# RN41_Rootooth.net
KiCad netlist of a schematic drawn in EAGLE
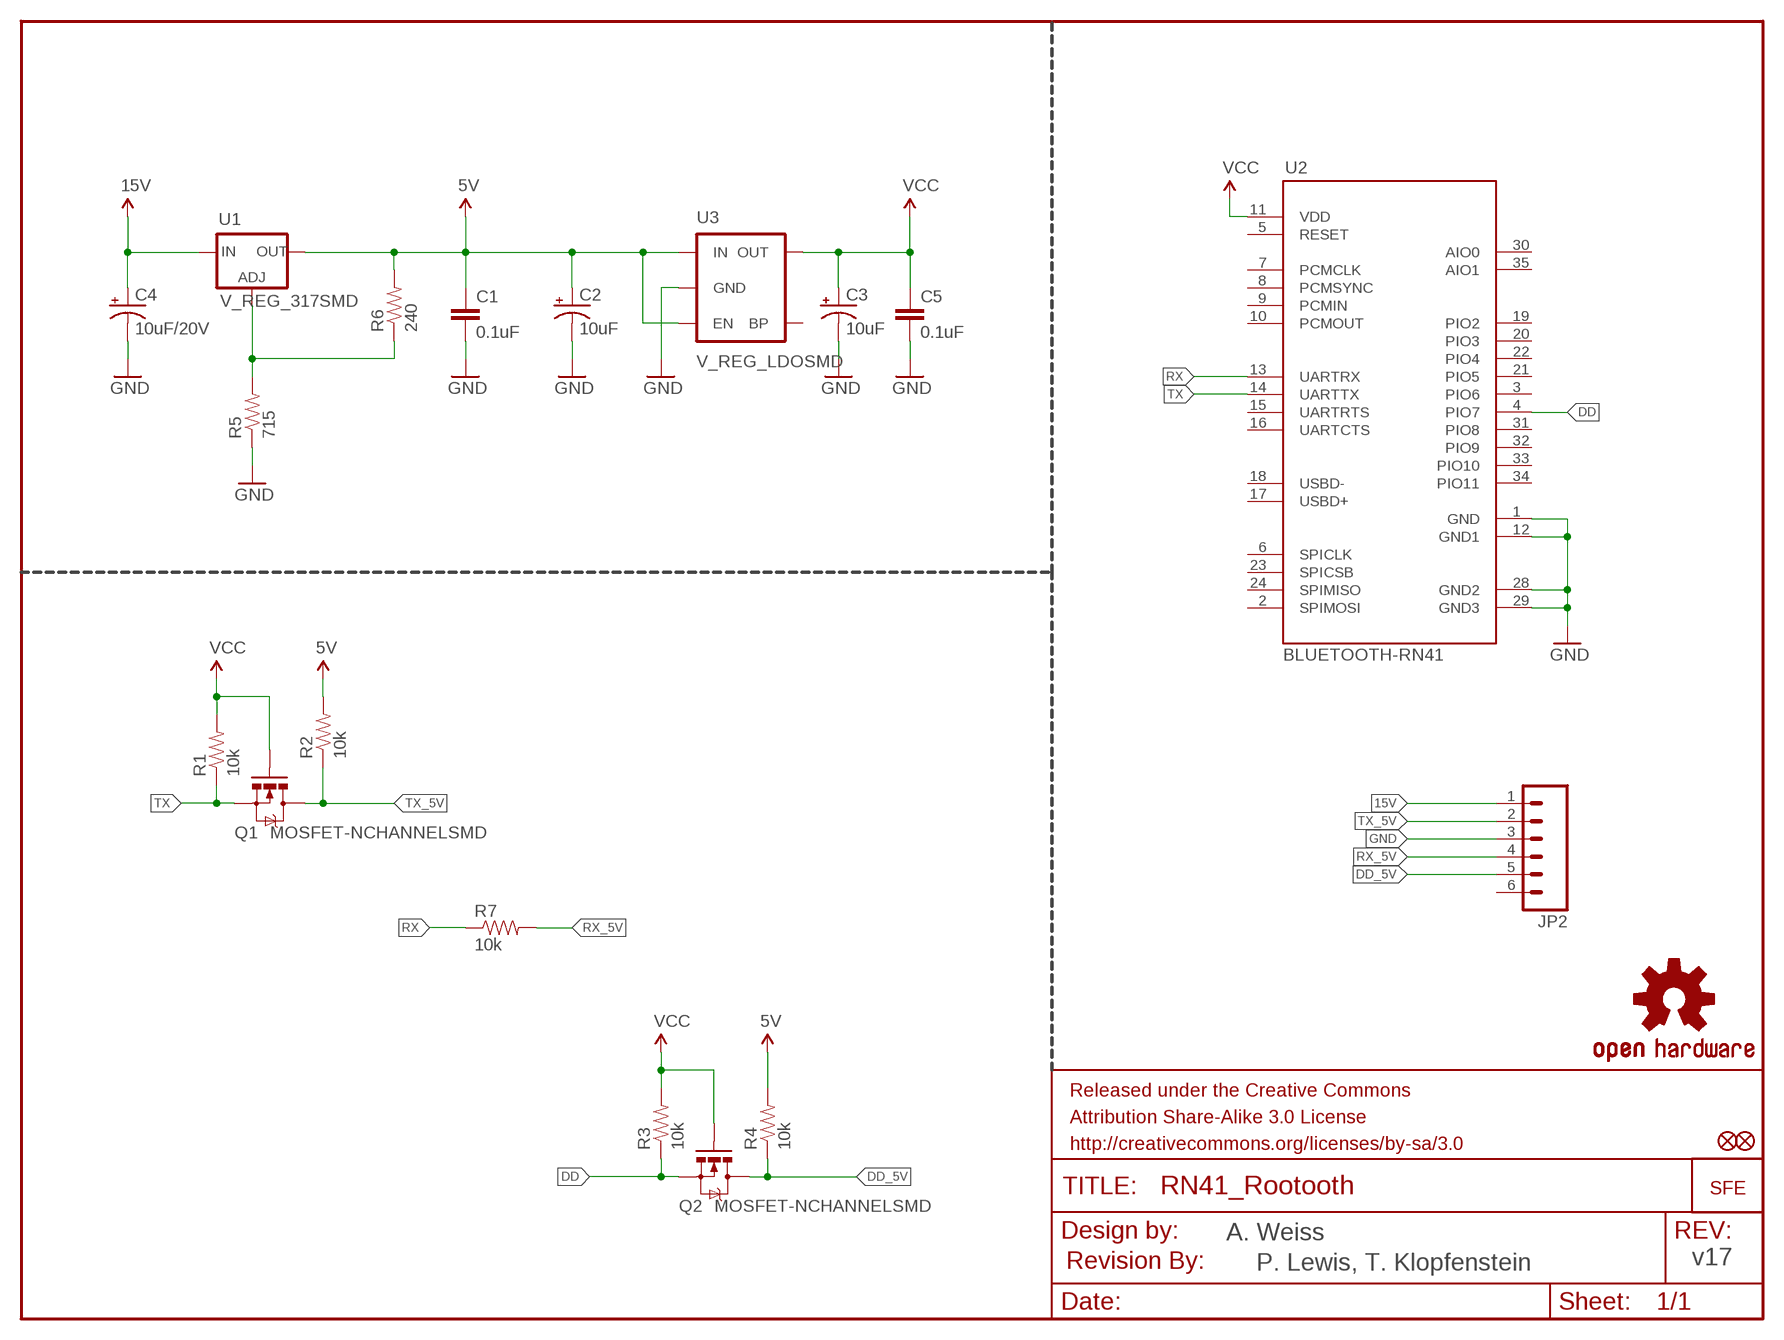
[diagram p0: schematic, sheet 1]

(export (version "E")
  (design (tool "Eeschema 10.0.6"))
  (components
    (comp (ref "C1")
      (value "0.1uF")
      (footprint "eagle-import:0603-CAP")
      (libsource (lib "eagle-import") (part "CAP0603-CAP"))
    )
    (comp (ref "C2")
      (value "10uF")
      (footprint "eagle-import:EIA3216")
      (libsource (lib "eagle-import") (part "CAP_POL1206"))
    )
    (comp (ref "C3")
      (value "10uF")
      (footprint "eagle-import:EIA3216")
      (libsource (lib "eagle-import") (part "CAP_POL1206"))
    )
    (comp (ref "C4")
      (value "10uF/20V")
      (footprint "eagle-import:EIA3528")
      (libsource (lib "eagle-import") (part "CAP_POL3528"))
    )
    (comp (ref "C5")
      (value "0.1uF")
      (footprint "eagle-import:0603-CAP")
      (libsource (lib "eagle-import") (part "CAP0603-CAP"))
    )
    (comp (ref "FRAME1")
      (value "FRAME-LETTER")
      (footprint "eagle-import:CREATIVE_COMMONS")
      (libsource (lib "eagle-import") (part "FRAME-LETTER"))
    )
    (comp (ref "JP1")
      (value "FIDUCIALUFIDUCIAL")
      (footprint "eagle-import:MICRO-FIDUCIAL")
      (libsource (lib "eagle-import") (part "FIDUCIALUFIDUCIAL"))
    )
    (comp (ref "JP2")
      (value "M06SMD")
      (footprint "eagle-import:1X06-SMD")
      (libsource (lib "eagle-import") (part "M06SMD"))
    )
    (comp (ref "JP3")
      (value "FIDUCIALUFIDUCIAL")
      (footprint "eagle-import:MICRO-FIDUCIAL")
      (libsource (lib "eagle-import") (part "FIDUCIALUFIDUCIAL"))
    )
    (comp (ref "LOGO1")
      (value "OSHW-LOGOS")
      (footprint "eagle-import:OSHW-LOGO-S")
      (libsource (lib "eagle-import") (part "OSHW-LOGOS"))
    )
    (comp (ref "Q1")
      (value "MOSFET-NCHANNELSMD")
      (footprint "eagle-import:SOT23-3")
      (libsource (lib "eagle-import") (part "MOSFET-NCHANNELSMD"))
    )
    (comp (ref "Q2")
      (value "MOSFET-NCHANNELSMD")
      (footprint "eagle-import:SOT23-3")
      (libsource (lib "eagle-import") (part "MOSFET-NCHANNELSMD"))
    )
    (comp (ref "R1")
      (value "10k")
      (footprint "eagle-import:0603-RES")
      (libsource (lib "eagle-import") (part "RESISTOR0603-RES"))
    )
    (comp (ref "R2")
      (value "10k")
      (footprint "eagle-import:0603-RES")
      (libsource (lib "eagle-import") (part "RESISTOR0603-RES"))
    )
    (comp (ref "R3")
      (value "10k")
      (footprint "eagle-import:0603-RES")
      (libsource (lib "eagle-import") (part "RESISTOR0603-RES"))
    )
    (comp (ref "R4")
      (value "10k")
      (footprint "eagle-import:0603-RES")
      (libsource (lib "eagle-import") (part "RESISTOR0603-RES"))
    )
    (comp (ref "R5")
      (value "715")
      (footprint "eagle-import:0603-RES")
      (libsource (lib "eagle-import") (part "RESISTOR0603-RES"))
    )
    (comp (ref "R6")
      (value "240")
      (footprint "eagle-import:0603-RES")
      (libsource (lib "eagle-import") (part "RESISTOR0603-RES"))
    )
    (comp (ref "R7")
      (value "10k")
      (footprint "eagle-import:0603-RES")
      (libsource (lib "eagle-import") (part "RESISTOR0603-RES"))
    )
    (comp (ref "U$1")
      (value "LOGO-SFENEW")
      (footprint "eagle-import:SFE-NEW-WEBLOGO")
      (libsource (lib "eagle-import") (part "LOGO-SFENEW"))
    )
    (comp (ref "U$2")
      (value "REVISION")
      (footprint "eagle-import:REVISION")
      (libsource (lib "eagle-import") (part "REVISION"))
    )
    (comp (ref "U1")
      (value "V_REG_317SMD")
      (footprint "eagle-import:SOT223")
      (libsource (lib "eagle-import") (part "V_REG_317SMD"))
    )
    (comp (ref "U2")
      (value "BLUETOOTH-RN41")
      (footprint "eagle-import:RN41")
      (libsource (lib "eagle-import") (part "BLUETOOTH-RN41{dblquote}"))
    )
    (comp (ref "U3")
      (value "V_REG_LDOSMD")
      (footprint "eagle-import:SOT23-5")
      (libsource (lib "eagle-import") (part "V_REG_LDOSMD"))
    )
  )
  (nets
    (net (code "1") (name "5V") (class "Default")
      (node (ref "C1") (pin "1") (pinfunction "1_1") (pintype "passive"))
      (node (ref "C2") (pin "A") (pinfunction "+_A") (pintype "passive"))
      (node (ref "R2") (pin "2") (pinfunction "2_2") (pintype "passive"))
      (node (ref "R4") (pin "2") (pinfunction "2_2") (pintype "passive"))
      (node (ref "R6") (pin "2") (pinfunction "2_2") (pintype "passive"))
      (node (ref "U1") (pin "2") (pinfunction "OUT_2") (pintype "output"))
      (node (ref "U3") (pin "1") (pinfunction "IN_1") (pintype "input"))
      (node (ref "U3") (pin "3") (pinfunction "EN_3") (pintype "input"))
    )
    (net (code "2") (name "15V") (class "Default")
      (node (ref "C4") (pin "A") (pinfunction "+_A") (pintype "passive"))
      (node (ref "JP2") (pin "1") (pinfunction "1_1") (pintype "passive"))
      (node (ref "U1") (pin "3") (pinfunction "IN_3") (pintype "input"))
    )
    (net (code "3") (name "DD") (class "Default")
      (node (ref "Q2") (pin "2") (pinfunction "S_2") (pintype "passive"))
      (node (ref "R3") (pin "1") (pinfunction "1_1") (pintype "passive"))
      (node (ref "U2") (pin "4") (pinfunction "PIO7_4") (pintype "bidirectional"))
    )
    (net (code "4") (name "DD_5V") (class "Default")
      (node (ref "JP2") (pin "5") (pinfunction "5_5") (pintype "passive"))
      (node (ref "Q2") (pin "3") (pinfunction "D_3") (pintype "passive"))
      (node (ref "R4") (pin "1") (pinfunction "1_1") (pintype "passive"))
    )
    (net (code "5") (name "GND") (class "Default")
      (node (ref "C1") (pin "2") (pinfunction "2_2") (pintype "passive"))
      (node (ref "C2") (pin "C") (pinfunction "-_C") (pintype "passive"))
      (node (ref "C3") (pin "C") (pinfunction "-_C") (pintype "passive"))
      (node (ref "C4") (pin "C") (pinfunction "-_C") (pintype "passive"))
      (node (ref "C5") (pin "2") (pinfunction "2_2") (pintype "passive"))
      (node (ref "JP2") (pin "3") (pinfunction "3_3") (pintype "passive"))
      (node (ref "R5") (pin "1") (pinfunction "1_1") (pintype "passive"))
      (node (ref "U2") (pin "1") (pinfunction "GND_1") (pintype "bidirectional"))
      (node (ref "U2") (pin "12") (pinfunction "GND1_12") (pintype "bidirectional"))
      (node (ref "U2") (pin "28") (pinfunction "GND2_28") (pintype "bidirectional"))
      (node (ref "U2") (pin "29") (pinfunction "GND3_29") (pintype "bidirectional"))
      (node (ref "U3") (pin "2") (pinfunction "GND_2") (pintype "input"))
    )
    (net (code "6") (name "Net-(U1-ADJ)") (class "Default")
      (node (ref "R5") (pin "2") (pinfunction "2_2") (pintype "passive"))
      (node (ref "R6") (pin "1") (pinfunction "1_1") (pintype "passive"))
      (node (ref "U1") (pin "1") (pinfunction "ADJ_1") (pintype "input"))
    )
    (net (code "7") (name "RX") (class "Default")
      (node (ref "R7") (pin "1") (pinfunction "1_1") (pintype "passive"))
      (node (ref "U2") (pin "13") (pinfunction "UARTRX_13") (pintype "bidirectional"))
    )
    (net (code "8") (name "RX_5V") (class "Default")
      (node (ref "JP2") (pin "4") (pinfunction "4_4") (pintype "passive"))
      (node (ref "R7") (pin "2") (pinfunction "2_2") (pintype "passive"))
    )
    (net (code "9") (name "TX") (class "Default")
      (node (ref "Q1") (pin "2") (pinfunction "S_2") (pintype "passive"))
      (node (ref "R1") (pin "1") (pinfunction "1_1") (pintype "passive"))
      (node (ref "U2") (pin "14") (pinfunction "UARTTX_14") (pintype "bidirectional"))
    )
    (net (code "10") (name "TX_5V") (class "Default")
      (node (ref "JP2") (pin "2") (pinfunction "2_2") (pintype "passive"))
      (node (ref "Q1") (pin "3") (pinfunction "D_3") (pintype "passive"))
      (node (ref "R2") (pin "1") (pinfunction "1_1") (pintype "passive"))
    )
    (net (code "11") (name "VCC") (class "Default")
      (node (ref "C3") (pin "A") (pinfunction "+_A") (pintype "passive"))
      (node (ref "C5") (pin "1") (pinfunction "1_1") (pintype "passive"))
      (node (ref "Q1") (pin "1") (pinfunction "G_1") (pintype "passive"))
      (node (ref "Q2") (pin "1") (pinfunction "G_1") (pintype "passive"))
      (node (ref "R1") (pin "2") (pinfunction "2_2") (pintype "passive"))
      (node (ref "R3") (pin "2") (pinfunction "2_2") (pintype "passive"))
      (node (ref "U2") (pin "11") (pinfunction "VDD_11") (pintype "bidirectional"))
      (node (ref "U3") (pin "5") (pinfunction "OUT_5") (pintype "passive"))
    )
    (net (code "12") (name "unconnected-(JP2-Pad6)") (class "Default")
      (node (ref "JP2") (pin "6") (pinfunction "6_6") (pintype "passive"))
    )
    (net (code "13") (name "unconnected-(U2-AIO0-Pad30)") (class "Default")
      (node (ref "U2") (pin "30") (pinfunction "AIO0_30") (pintype "bidirectional"))
    )
    (net (code "14") (name "unconnected-(U2-AIO1-Pad35)") (class "Default")
      (node (ref "U2") (pin "35") (pinfunction "AIO1_35") (pintype "bidirectional"))
    )
    (net (code "15") (name "unconnected-(U2-PCMCLK-Pad7)") (class "Default")
      (node (ref "U2") (pin "7") (pinfunction "PCMCLK_7") (pintype "bidirectional"))
    )
    (net (code "16") (name "unconnected-(U2-PCMIN-Pad9)") (class "Default")
      (node (ref "U2") (pin "9") (pinfunction "PCMIN_9") (pintype "bidirectional"))
    )
    (net (code "17") (name "unconnected-(U2-PCMOUT-Pad10)") (class "Default")
      (node (ref "U2") (pin "10") (pinfunction "PCMOUT_10") (pintype "bidirectional"))
    )
    (net (code "18") (name "unconnected-(U2-PCMSYNC-Pad8)") (class "Default")
      (node (ref "U2") (pin "8") (pinfunction "PCMSYNC_8") (pintype "bidirectional"))
    )
    (net (code "19") (name "unconnected-(U2-PIO2-Pad19)") (class "Default")
      (node (ref "U2") (pin "19") (pinfunction "PIO2_19") (pintype "bidirectional"))
    )
    (net (code "20") (name "unconnected-(U2-PIO3-Pad20)") (class "Default")
      (node (ref "U2") (pin "20") (pinfunction "PIO3_20") (pintype "bidirectional"))
    )
    (net (code "21") (name "unconnected-(U2-PIO4-Pad22)") (class "Default")
      (node (ref "U2") (pin "22") (pinfunction "PIO4_22") (pintype "bidirectional"))
    )
    (net (code "22") (name "unconnected-(U2-PIO5-Pad21)") (class "Default")
      (node (ref "U2") (pin "21") (pinfunction "PIO5_21") (pintype "bidirectional"))
    )
    (net (code "23") (name "unconnected-(U2-PIO6-Pad3)") (class "Default")
      (node (ref "U2") (pin "3") (pinfunction "PIO6_3") (pintype "bidirectional"))
    )
    (net (code "24") (name "unconnected-(U2-PIO8-Pad31)") (class "Default")
      (node (ref "U2") (pin "31") (pinfunction "PIO8_31") (pintype "bidirectional"))
    )
    (net (code "25") (name "unconnected-(U2-PIO9-Pad32)") (class "Default")
      (node (ref "U2") (pin "32") (pinfunction "PIO9_32") (pintype "bidirectional"))
    )
    (net (code "26") (name "unconnected-(U2-PIO10-Pad33)") (class "Default")
      (node (ref "U2") (pin "33") (pinfunction "PIO10_33") (pintype "bidirectional"))
    )
    (net (code "27") (name "unconnected-(U2-PIO11-Pad34)") (class "Default")
      (node (ref "U2") (pin "34") (pinfunction "PIO11_34") (pintype "bidirectional"))
    )
    (net (code "28") (name "unconnected-(U2-RESET-Pad5)") (class "Default")
      (node (ref "U2") (pin "5") (pinfunction "RESET_5") (pintype "bidirectional"))
    )
    (net (code "29") (name "unconnected-(U2-SPICLK-Pad6)") (class "Default")
      (node (ref "U2") (pin "6") (pinfunction "SPICLK_6") (pintype "bidirectional"))
    )
    (net (code "30") (name "unconnected-(U2-SPICSB-Pad23)") (class "Default")
      (node (ref "U2") (pin "23") (pinfunction "SPICSB_23") (pintype "bidirectional"))
    )
    (net (code "31") (name "unconnected-(U2-SPIMISO-Pad24)") (class "Default")
      (node (ref "U2") (pin "24") (pinfunction "SPIMISO_24") (pintype "bidirectional"))
    )
    (net (code "32") (name "unconnected-(U2-SPIMOSI-Pad2)") (class "Default")
      (node (ref "U2") (pin "2") (pinfunction "SPIMOSI_2") (pintype "bidirectional"))
    )
    (net (code "33") (name "unconnected-(U2-UARTCTS-Pad16)") (class "Default")
      (node (ref "U2") (pin "16") (pinfunction "UARTCTS_16") (pintype "bidirectional"))
    )
    (net (code "34") (name "unconnected-(U2-UARTRTS-Pad15)") (class "Default")
      (node (ref "U2") (pin "15") (pinfunction "UARTRTS_15") (pintype "bidirectional"))
    )
    (net (code "35") (name "unconnected-(U2-USBD+-Pad17)") (class "Default")
      (node (ref "U2") (pin "17") (pinfunction "USBD+_17") (pintype "bidirectional"))
    )
    (net (code "36") (name "unconnected-(U2-USBD--Pad18)") (class "Default")
      (node (ref "U2") (pin "18") (pinfunction "USBD-_18") (pintype "bidirectional"))
    )
    (net (code "37") (name "unconnected-(U3-BP-Pad4)") (class "Default")
      (node (ref "U3") (pin "4") (pinfunction "BP_4") (pintype "input"))
    )
  )
)
